# GNSS_FE.net
KiCad netlist of a schematic drawn in Altium Designer
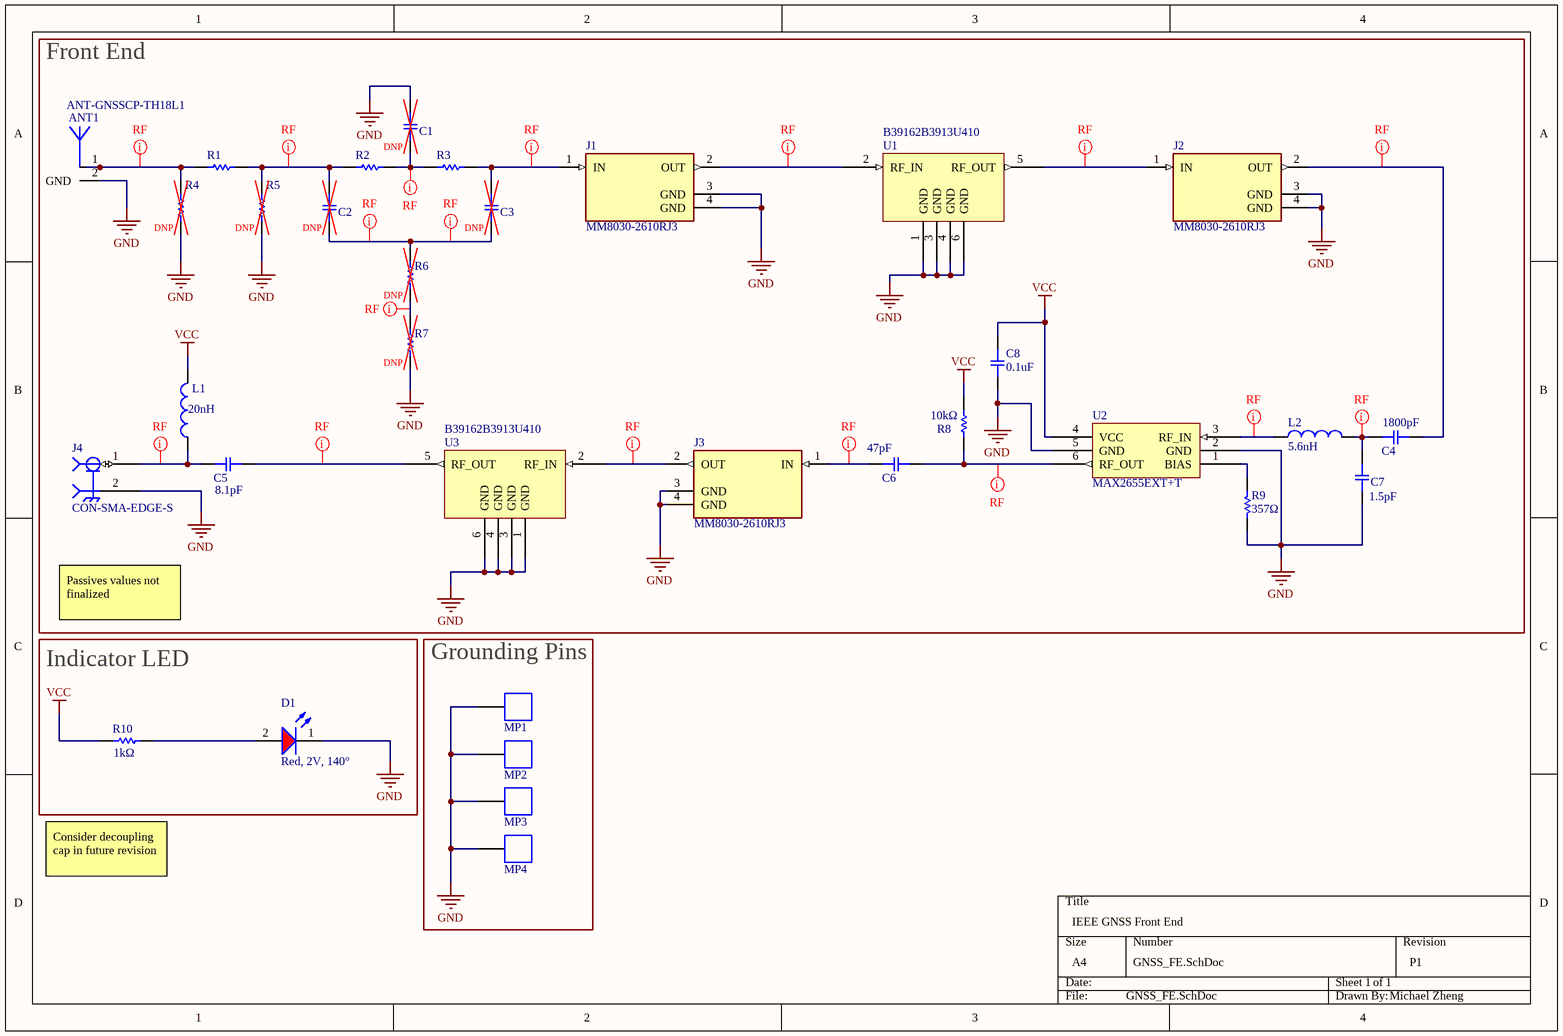
[diagram p0: GNSS_FE.SchDoc]

(export (version "E")
  (design (tool "Eeschema 10.0.6"))
  (components
    (comp (ref "ANT1")
      (value "ANT-GNSSCP-TH18L1")
      (footprint "ANT-GNSSCP-TH18L1")
      (description "CERAMIC PATCH GNSS ANTENNA")
      (libsource (lib "Symbols") (part "ANT-GNSSCP-TH18L1"))
    )
    (comp (ref "C1")
      (value "GRM1555C1H102JA01D")
      (footprint "0402_CAP")
      (description "CAP CER 1000PF 50V C0G/NP0 0402")
      (libsource (lib "Symbols") (part "GRM1555C1H102JA01D"))
    )
    (comp (ref "C2")
      (value "GRM1555C1H102JA01D")
      (footprint "0402_CAP")
      (description "CAP CER 1000PF 50V C0G/NP0 0402")
      (libsource (lib "Symbols") (part "GRM1555C1H102JA01D"))
    )
    (comp (ref "C3")
      (value "GRM1555C1H102JA01D")
      (footprint "0402_CAP")
      (description "CAP CER 1000PF 50V C0G/NP0 0402")
      (libsource (lib "Symbols") (part "GRM1555C1H102JA01D"))
    )
    (comp (ref "C4")
      (value "GRM1555C1H182JA01D")
      (footprint "0402_CAP")
      (description "CAP CER 1800PF 50V C0G/NP0 0402")
      (fields (field (name "CAPACITANCE") "1800pF"))
      (libsource (lib "Symbols") (part "GRM1555C1H102JA01D"))
    )
    (comp (ref "C5")
      (value "GJM1555C1H8R1BB01D")
      (footprint "0402_CAP")
      (description "CAP CER 8.1PF 50V C0G/NP0 0402")
      (fields (field (name "CAPACITANCE") "8.1pF"))
      (libsource (lib "Symbols") (part "GRM1555C1H102JA01D"))
    )
    (comp (ref "C6")
      (value "GJM1555C1H470FB01D")
      (footprint "0402_CAP")
      (description "CAP CER 47PF 50V C0G/NP0 0402")
      (fields (field (name "CAPACITANCE") "47pF"))
      (libsource (lib "Symbols") (part "GRM1555C1H102JA01D"))
    )
    (comp (ref "C7")
      (value "GJM1555C1H1R5WB01D")
      (footprint "0402_CAP")
      (description "CAP CER 1.5PF 50V C0G/NP0 0402")
      (fields (field (name "CAPACITANCE") "1.5pF"))
      (libsource (lib "Symbols") (part "GRM1555C1H102JA01D"))
    )
    (comp (ref "C8")
      (value "GCM188L81H104KA57D")
      (footprint "CAP_MURATA_0603")
      (description "CAP CER 0.1UF 50V X8L 0603")
      (fields (field (name "CAPACITANCE") "0.1uF"))
      (libsource (lib "Symbols") (part "GCM188L81H104KA57D"))
    )
    (comp (ref "D1")
      (value "Red, 2V, 140°")
      (footprint "WL-SMCW")
      (description "WL-SMCW Mono-color Chip LED Waterclear, SMT, size 0603, Red, 2V, 140°")
      (fields
        (field (name "MANUFACTURER PART NUMBER") "150060RS75000")
        (field (name "MANUFACTURER") "Wurth Elektronik")
      )
      (libsource (lib "Symbols") (part "150060RS75000"))
    )
    (comp (ref "J1")
      (value "MM8030-2610RJ3")
      (footprint "MURATA_MM8030-2610RJ3")
      (description "SWG Connector Receptacle, Female Socket 50Ohm Surface Mount Solder")
      (fields (field (name "MF") "Murata") (field (name "DIGI-KEY_PART_NUMBER") "490-5907-1-ND"))
      (libsource (lib "Symbols") (part "MM8030-2610RJ3"))
    )
    (comp (ref "J2")
      (value "MM8030-2610RJ3")
      (footprint "MURATA_MM8030-2610RJ3")
      (description "SWG Connector Receptacle, Female Socket 50Ohm Surface Mount Solder")
      (fields (field (name "MF") "Murata") (field (name "DIGI-KEY_PART_NUMBER") "490-5907-1-ND"))
      (libsource (lib "Symbols") (part "MM8030-2610RJ3"))
    )
    (comp (ref "J3")
      (value "MM8030-2610RJ3")
      (footprint "MURATA_MM8030-2610RJ3")
      (description "SWG Connector Receptacle, Female Socket 50Ohm Surface Mount Solder")
      (fields (field (name "MF") "Murata") (field (name "DIGI-KEY_PART_NUMBER") "490-5907-1-ND"))
      (libsource (lib "") (part "MM8030-2610RJ3_1"))
    )
    (comp (ref "J4")
      (value "CON-SMA-EDGE-S")
      (footprint "RFSOLUTIONS_CON-SMA-EDGE-S")
      (description "CONN SMA JACK STR EDGE MNT")
      (libsource (lib "Symbols") (part "CON-SMA-EDGE-S"))
    )
    (comp (ref "L1")
      (value "20nH")
      (footprint "INDC1006X60N")
      (description "FIXED IND 20NH 800MA 0.186OHM SM")
      (fields (field (name "MP") "LQW15AN3N6C10D") (field (name "Comment") "LQW15AN20NG8ZD"))
      (libsource (lib "Symbols") (part "LQW15AN3N6C10D"))
    )
    (comp (ref "L2")
      (value "5.6nH")
      (footprint "INDC1006X60N")
      (description "FIXED IND 5.6NH 600MA 0.18OHM SM")
      (fields (field (name "MP") "LQW15AN3N6C10D") (field (name "Comment") "LQG15HN5N6C02D"))
      (libsource (lib "Symbols") (part "LQW15AN3N6C10D"))
    )
    (comp (ref "MP1")
      (value "36900000")
      (footprint "36900000")
      (description "WE-SHC Shielding Cabinet, Clip, Tin Plated, Tape and Reel, 6.5x0.8x1.27mm")
      (fields (field (name "MANUFACTURER") "Wurth Elektronik"))
      (libsource (lib "Symbols") (part "36900000"))
    )
    (comp (ref "MP2")
      (value "36900000")
      (footprint "36900000")
      (description "WE-SHC Shielding Cabinet, Clip, Tin Plated, Tape and Reel, 6.5x0.8x1.27mm")
      (fields (field (name "MANUFACTURER") "Wurth Elektronik"))
      (libsource (lib "Symbols") (part "36900000"))
    )
    (comp (ref "MP3")
      (value "36900000")
      (footprint "36900000")
      (description "WE-SHC Shielding Cabinet, Clip, Tin Plated, Tape and Reel, 6.5x0.8x1.27mm")
      (fields (field (name "MANUFACTURER") "Wurth Elektronik"))
      (libsource (lib "Symbols") (part "36900000"))
    )
    (comp (ref "MP4")
      (value "36900000")
      (footprint "36900000")
      (description "WE-SHC Shielding Cabinet, Clip, Tin Plated, Tape and Reel, 6.5x0.8x1.27mm")
      (fields (field (name "MANUFACTURER") "Wurth Elektronik"))
      (libsource (lib "Symbols") (part "36900000"))
    )
    (comp (ref "R1")
      (value "RC0402JR-070RL")
      (footprint "0402_CAP")
      (description "RES 0 OHM JUMPER 1/16W 0402")
      (fields (field (name "TOLERANCE") "5%") (field (name "MANUFACTURER") "Yageo"))
      (libsource (lib "Symbols") (part "RC0402JR-070RL"))
    )
    (comp (ref "R2")
      (value "RC0402JR-070RL")
      (footprint "0402_CAP")
      (description "RES 0 OHM JUMPER 1/16W 0402")
      (fields (field (name "TOLERANCE") "5%") (field (name "MANUFACTURER") "Yageo"))
      (libsource (lib "Symbols") (part "RC0402JR-070RL"))
    )
    (comp (ref "R3")
      (value "RC0402JR-070RL")
      (footprint "0402_CAP")
      (description "RES 0 OHM JUMPER 1/16W 0402")
      (fields (field (name "TOLERANCE") "5%") (field (name "MANUFACTURER") "Yageo"))
      (libsource (lib "Symbols") (part "RC0402JR-070RL"))
    )
    (comp (ref "R4")
      (value "RC0402JR-070RL")
      (footprint "0402_CAP")
      (description "RES 0 OHM JUMPER 1/16W 0402")
      (fields (field (name "TOLERANCE") "5%") (field (name "MANUFACTURER") "Yageo"))
      (libsource (lib "Symbols") (part "RC0402JR-070RL"))
    )
    (comp (ref "R5")
      (value "RC0402JR-070RL")
      (footprint "0402_CAP")
      (description "RES 0 OHM JUMPER 1/16W 0402")
      (fields (field (name "TOLERANCE") "5%") (field (name "MANUFACTURER") "Yageo"))
      (libsource (lib "Symbols") (part "RC0402JR-070RL"))
    )
    (comp (ref "R6")
      (value "RC0402JR-070RL")
      (footprint "0402_CAP")
      (description "RES 0 OHM JUMPER 1/16W 0402")
      (fields (field (name "TOLERANCE") "5%") (field (name "MANUFACTURER") "Yageo"))
      (libsource (lib "Symbols") (part "RC0402JR-070RL"))
    )
    (comp (ref "R7")
      (value "RC0402JR-070RL")
      (footprint "0402_CAP")
      (description "RES 0 OHM JUMPER 1/16W 0402")
      (fields (field (name "TOLERANCE") "5%") (field (name "MANUFACTURER") "Yageo"))
      (libsource (lib "Symbols") (part "RC0402JR-070RL"))
    )
    (comp (ref "R8")
      (value "RC0402FR-0710KL")
      (footprint "0402_CAP")
      (description "RES 10K OHM 1% 1/16W 0402")
      (fields
        (field (name "TOLERANCE") "5%")
        (field (name "RESISTANCE") "10kΩ")
        (field (name "MANUFACTURER") "Yageo")
      )
      (libsource (lib "Symbols") (part "RC0402JR-070RL"))
    )
    (comp (ref "R9")
      (value "RC0402FR-07357RL")
      (footprint "RC0603JR-070RL")
      (description "RES 357 OHM 1% 1/16W 0402")
      (fields
        (field (name "TOLERANCE") "5%")
        (field (name "RESISTANCE") "357Ω")
        (field (name "MANUFACTURER") "Yageo")
      )
      (libsource (lib "Symbols") (part "RC0603JR-070RL"))
    )
    (comp (ref "R10")
      (value "RC0603FR-071KL")
      (footprint "RC0603JR-070RL")
      (description "1 kOhms ±1% 0.1W, 1/10W Chip Resistor 0603 (1608 Metric) Moisture Resistant Thick Film")
      (fields
        (field (name "TOLERANCE") "5%")
        (field (name "RESISTANCE") "1kΩ")
        (field (name "MANUFACTURER") "Yageo")
      )
      (libsource (lib "Symbols") (part "RC0603JR-070RL"))
    )
    (comp (ref "U1")
      (value "B39162B3913U410")
      (footprint "B39162B3913U410")
      (description "FILTER SAW 1.588GHZ 6SMD")
      (libsource (lib "Symbols") (part "B39162B3913U410"))
    )
    (comp (ref "U2")
      (value "MAX2655EXT+T")
      (footprint "MAX2655EXT+T")
      (description "IC AMP GPS 1.4GHZ-1.7GHZ SC70-6")
      (libsource (lib "Symbols") (part "MAX2655EXT+T"))
    )
    (comp (ref "U3")
      (value "B39162B3913U410")
      (footprint "B39162B3913U410")
      (description "FILTER SAW 1.588GHZ 6SMD")
      (libsource (lib "") (part "B39162B3913U410_1"))
    )
  )
  (nets
    (net (code "1") (name "GND") (class "Default")
      (node (ref "ANT1") (pin "2") (pinfunction "GND_2") (pintype "passive"))
      (node (ref "C1") (pin "2") (pinfunction "2_2") (pintype "passive"))
      (node (ref "C7") (pin "1") (pinfunction "1_1") (pintype "passive"))
      (node (ref "C8") (pin "1") (pinfunction "1_1") (pintype "passive"))
      (node (ref "D1") (pin "1") (pinfunction "K_1") (pintype "passive"))
      (node (ref "J1") (pin "3") (pinfunction "GND_3") (pintype "power_in"))
      (node (ref "J1") (pin "4") (pinfunction "GND_4") (pintype "power_in"))
      (node (ref "J2") (pin "3") (pinfunction "GND_3") (pintype "power_in"))
      (node (ref "J2") (pin "4") (pinfunction "GND_4") (pintype "power_in"))
      (node (ref "J3") (pin "3") (pinfunction "GND_3") (pintype "power_in"))
      (node (ref "J3") (pin "4") (pinfunction "GND_4") (pintype "power_in"))
      (node (ref "J4") (pin "2") (pinfunction "GND_2") (pintype "power_in"))
      (node (ref "MP1") (pin "1") (pinfunction "1_1") (pintype "passive"))
      (node (ref "MP2") (pin "1") (pinfunction "1_1") (pintype "passive"))
      (node (ref "MP3") (pin "1") (pinfunction "1_1") (pintype "passive"))
      (node (ref "MP4") (pin "1") (pinfunction "1_1") (pintype "passive"))
      (node (ref "R4") (pin "1") (pinfunction "1_1") (pintype "passive"))
      (node (ref "R5") (pin "1") (pinfunction "1_1") (pintype "passive"))
      (node (ref "R7") (pin "2") (pinfunction "2_2") (pintype "passive"))
      (node (ref "R9") (pin "2") (pinfunction "2_2") (pintype "passive"))
      (node (ref "U1") (pin "1") (pinfunction "GND_1") (pintype "power_in"))
      (node (ref "U1") (pin "3") (pinfunction "GND_3") (pintype "power_in"))
      (node (ref "U1") (pin "4") (pinfunction "GND_4") (pintype "power_in"))
      (node (ref "U1") (pin "6") (pinfunction "GND_6") (pintype "power_in"))
      (node (ref "U2") (pin "2") (pinfunction "GND_2") (pintype "power_in"))
      (node (ref "U2") (pin "5") (pinfunction "GND_5") (pintype "power_in"))
      (node (ref "U3") (pin "1") (pinfunction "GND_1") (pintype "power_in"))
      (node (ref "U3") (pin "3") (pinfunction "GND_3") (pintype "power_in"))
      (node (ref "U3") (pin "4") (pinfunction "GND_4") (pintype "power_in"))
      (node (ref "U3") (pin "6") (pinfunction "GND_6") (pintype "power_in"))
    )
    (net (code "2") (name "Net-(ANT1-RF_IN)") (class "Default")
      (node (ref "ANT1") (pin "1") (pinfunction "RF_IN_1") (pintype "passive"))
      (node (ref "R1") (pin "2") (pinfunction "2_2") (pintype "passive"))
      (node (ref "R4") (pin "2") (pinfunction "2_2") (pintype "passive"))
    )
    (net (code "3") (name "Net-(C1-Pad1)") (class "Default")
      (node (ref "C1") (pin "1") (pinfunction "1_1") (pintype "passive"))
      (node (ref "R2") (pin "1") (pinfunction "1_1") (pintype "passive"))
      (node (ref "R3") (pin "2") (pinfunction "2_2") (pintype "passive"))
    )
    (net (code "4") (name "Net-(C2-Pad1)") (class "Default")
      (node (ref "C2") (pin "1") (pinfunction "1_1") (pintype "passive"))
      (node (ref "C3") (pin "1") (pinfunction "1_1") (pintype "passive"))
      (node (ref "R6") (pin "1") (pinfunction "1_1") (pintype "passive"))
    )
    (net (code "5") (name "Net-(C2-Pad2)") (class "Default")
      (node (ref "C2") (pin "2") (pinfunction "2_2") (pintype "passive"))
      (node (ref "R1") (pin "1") (pinfunction "1_1") (pintype "passive"))
      (node (ref "R2") (pin "2") (pinfunction "2_2") (pintype "passive"))
      (node (ref "R5") (pin "2") (pinfunction "2_2") (pintype "passive"))
    )
    (net (code "6") (name "Net-(C4-Pad2)") (class "Default")
      (node (ref "C4") (pin "2") (pinfunction "2_2") (pintype "passive"))
      (node (ref "C7") (pin "2") (pinfunction "2_2") (pintype "passive"))
      (node (ref "L2") (pin "2") (pinfunction "2_2") (pintype "passive"))
    )
    (net (code "7") (name "Net-(D1-A)") (class "Default")
      (node (ref "D1") (pin "2") (pinfunction "A_2") (pintype "passive"))
      (node (ref "R10") (pin "2") (pinfunction "2_2") (pintype "passive"))
    )
    (net (code "8") (name "Net-(J1-IN)") (class "Default")
      (node (ref "C3") (pin "2") (pinfunction "2_2") (pintype "passive"))
      (node (ref "J1") (pin "1") (pinfunction "IN_1") (pintype "input"))
      (node (ref "R3") (pin "1") (pinfunction "1_1") (pintype "passive"))
    )
    (net (code "9") (name "Net-(J1-OUT)") (class "Default")
      (node (ref "J1") (pin "2") (pinfunction "OUT_2") (pintype "output"))
      (node (ref "U1") (pin "2") (pinfunction "RF_IN_2") (pintype "input"))
    )
    (net (code "10") (name "Net-(J2-IN)") (class "Default")
      (node (ref "J2") (pin "1") (pinfunction "IN_1") (pintype "input"))
      (node (ref "U1") (pin "5") (pinfunction "RF_OUT_5") (pintype "output"))
    )
    (net (code "11") (name "Net-(J2-OUT)") (class "Default")
      (node (ref "C4") (pin "1") (pinfunction "1_1") (pintype "passive"))
      (node (ref "J2") (pin "2") (pinfunction "OUT_2") (pintype "output"))
    )
    (net (code "12") (name "Net-(J3-IN)") (class "Default")
      (node (ref "C6") (pin "2") (pinfunction "2_2") (pintype "passive"))
      (node (ref "J3") (pin "1") (pinfunction "IN_1") (pintype "input"))
    )
    (net (code "13") (name "Net-(J3-OUT)") (class "Default")
      (node (ref "J3") (pin "2") (pinfunction "OUT_2") (pintype "output"))
      (node (ref "U3") (pin "2") (pinfunction "RF_IN_2") (pintype "input"))
    )
    (net (code "14") (name "Net-(J4-RF)") (class "Default")
      (node (ref "C5") (pin "2") (pinfunction "2_2") (pintype "passive"))
      (node (ref "J4") (pin "1") (pinfunction "RF_1") (pintype "bidirectional"))
      (node (ref "L1") (pin "1") (pinfunction "1_1") (pintype "passive"))
    )
    (net (code "15") (name "Net-(R6-Pad2)") (class "Default")
      (node (ref "R6") (pin "2") (pinfunction "2_2") (pintype "passive"))
      (node (ref "R7") (pin "1") (pinfunction "1_1") (pintype "passive"))
    )
    (net (code "16") (name "Net-(U2-BIAS)") (class "Default")
      (node (ref "R9") (pin "1") (pinfunction "1_1") (pintype "passive"))
      (node (ref "U2") (pin "1") (pinfunction "BIAS_1") (pintype "passive"))
    )
    (net (code "17") (name "Net-(U2-RF_IN)") (class "Default")
      (node (ref "L2") (pin "1") (pinfunction "1_1") (pintype "passive"))
      (node (ref "U2") (pin "3") (pinfunction "RF_IN_3") (pintype "input"))
    )
    (net (code "18") (name "Net-(U2-RF_OUT)") (class "Default")
      (node (ref "C6") (pin "1") (pinfunction "1_1") (pintype "passive"))
      (node (ref "R8") (pin "2") (pinfunction "2_2") (pintype "passive"))
      (node (ref "U2") (pin "6") (pinfunction "RF_OUT_6") (pintype "output"))
    )
    (net (code "19") (name "Net-(U3-RF_OUT)") (class "Default")
      (node (ref "C5") (pin "1") (pinfunction "1_1") (pintype "passive"))
      (node (ref "U3") (pin "5") (pinfunction "RF_OUT_5") (pintype "output"))
    )
    (net (code "20") (name "VCC") (class "Default")
      (node (ref "C8") (pin "2") (pinfunction "2_2") (pintype "passive"))
      (node (ref "L1") (pin "2") (pinfunction "2_2") (pintype "passive"))
      (node (ref "R10") (pin "1") (pinfunction "1_1") (pintype "passive"))
      (node (ref "R8") (pin "1") (pinfunction "1_1") (pintype "passive"))
      (node (ref "U2") (pin "4") (pinfunction "VCC_4") (pintype "power_in"))
    )
  )
)
